# EDCPSU.net
KiCad netlist of a schematic drawn in EAGLE
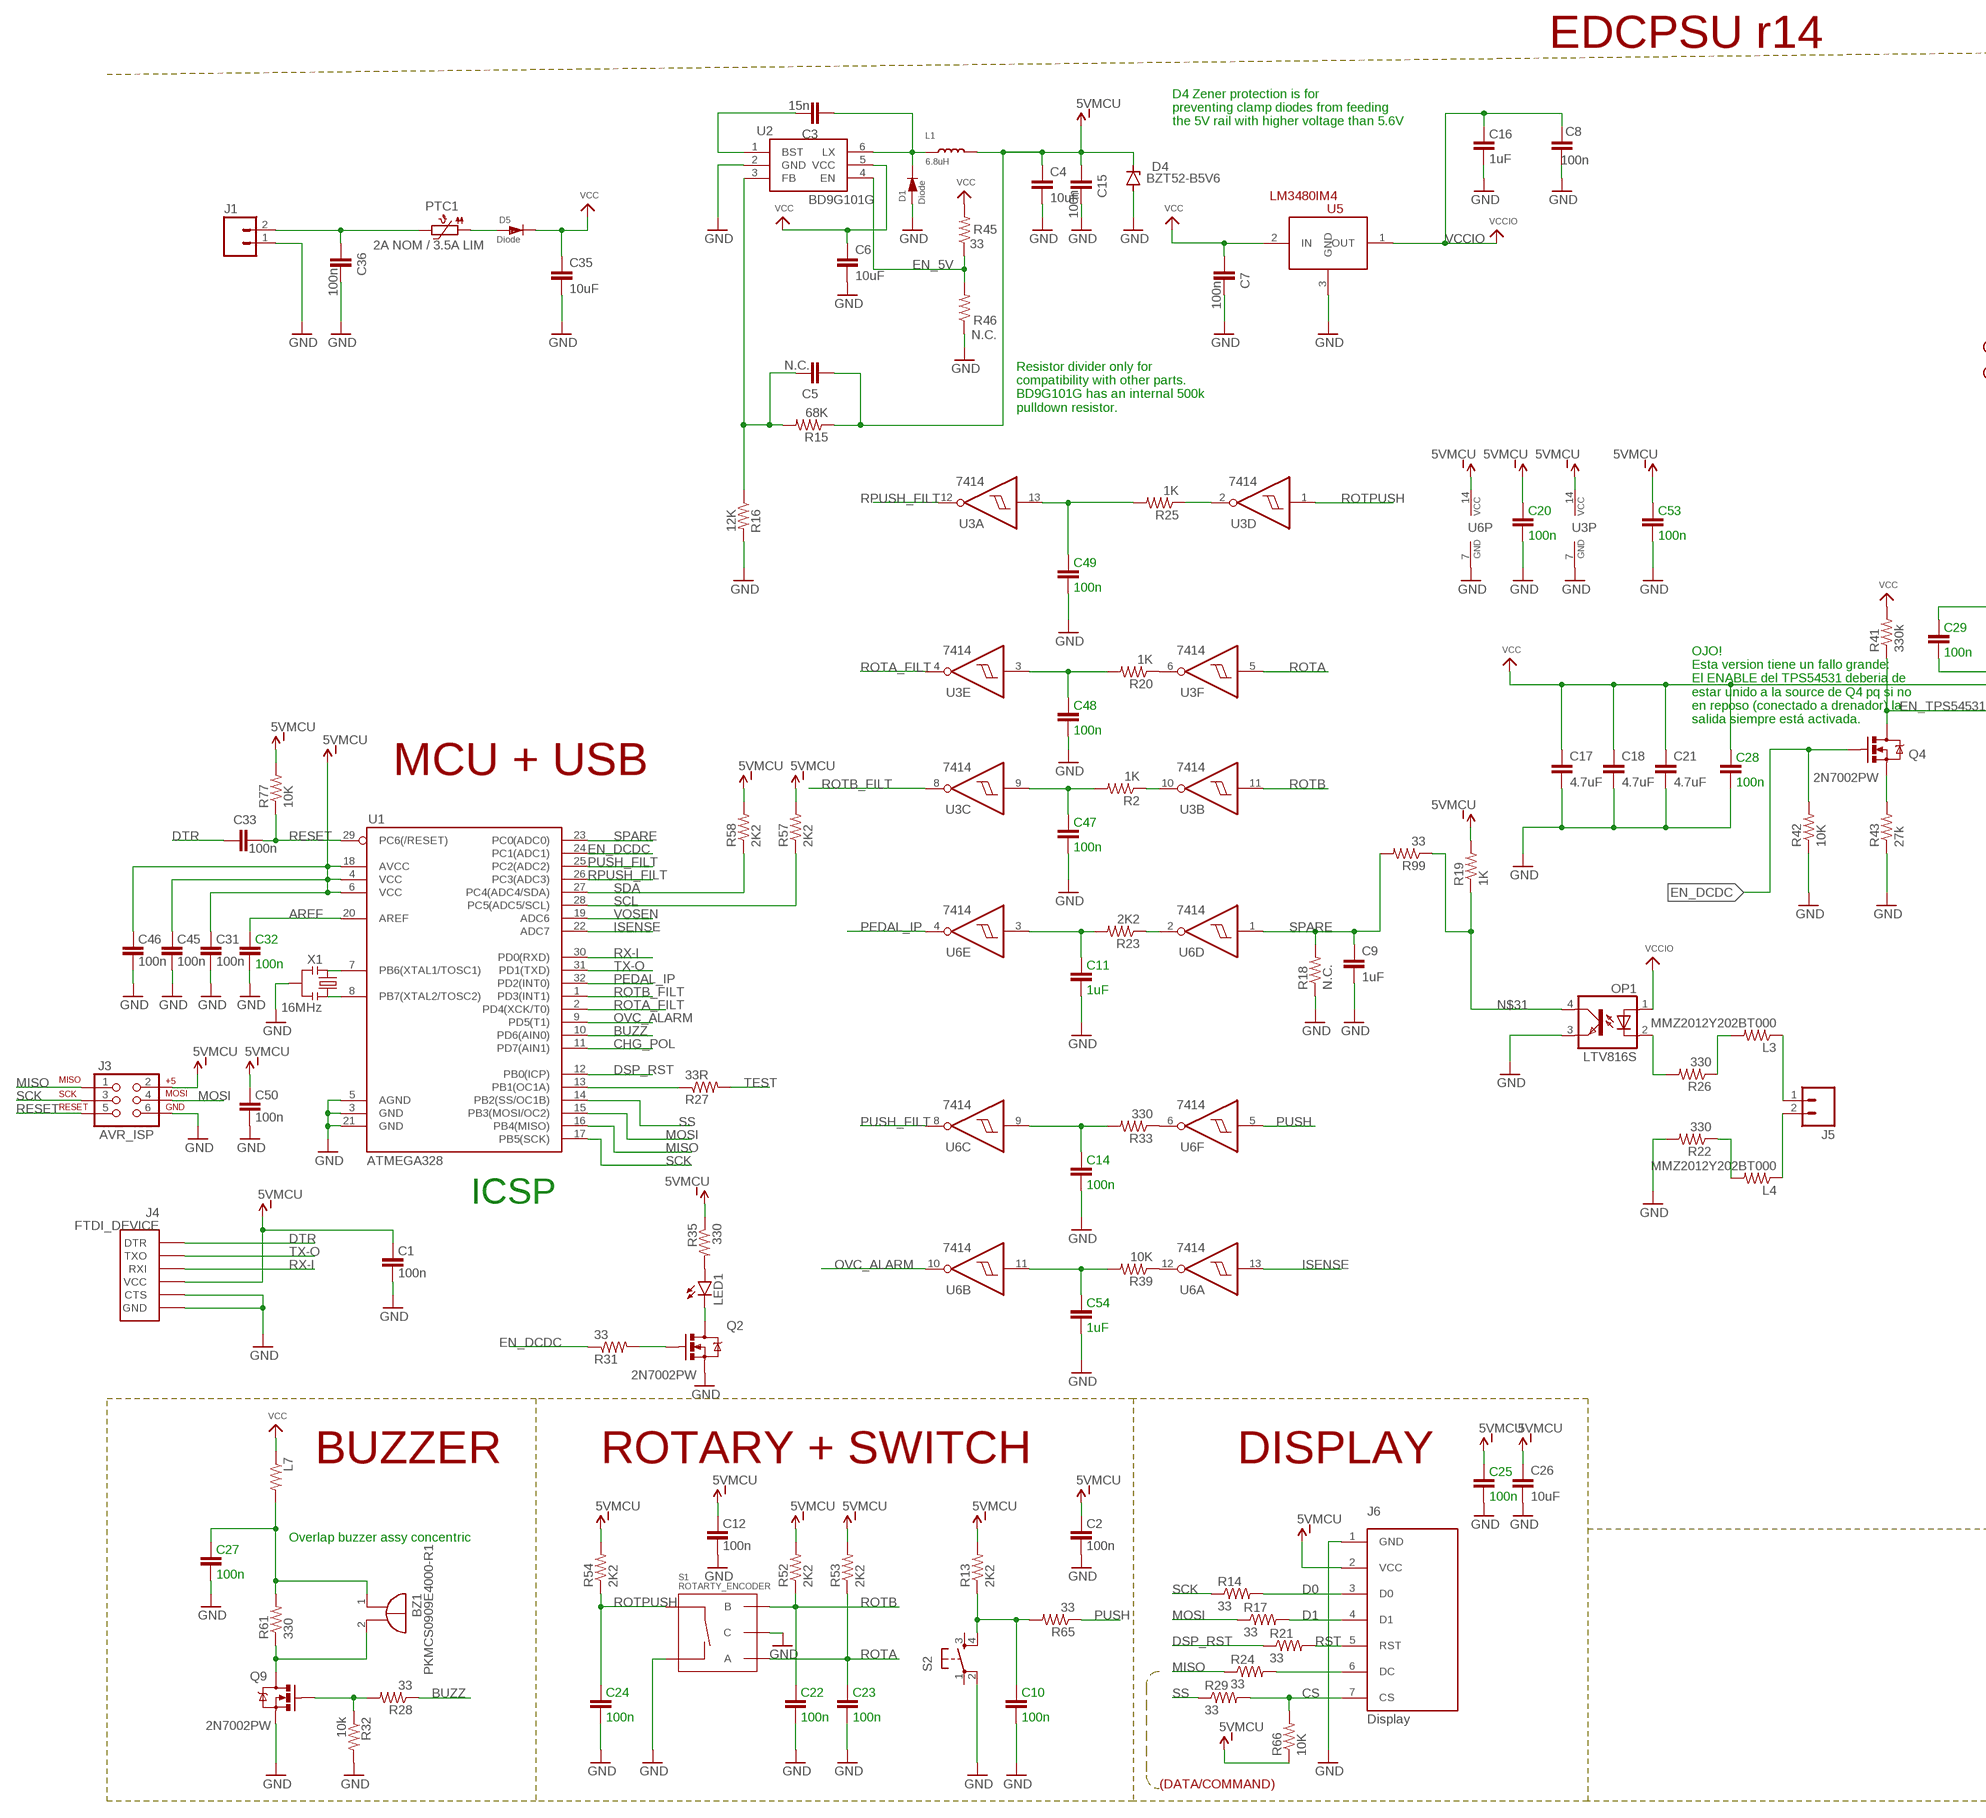
[diagram p0: schematic, sheet 1, part 1 of 2]
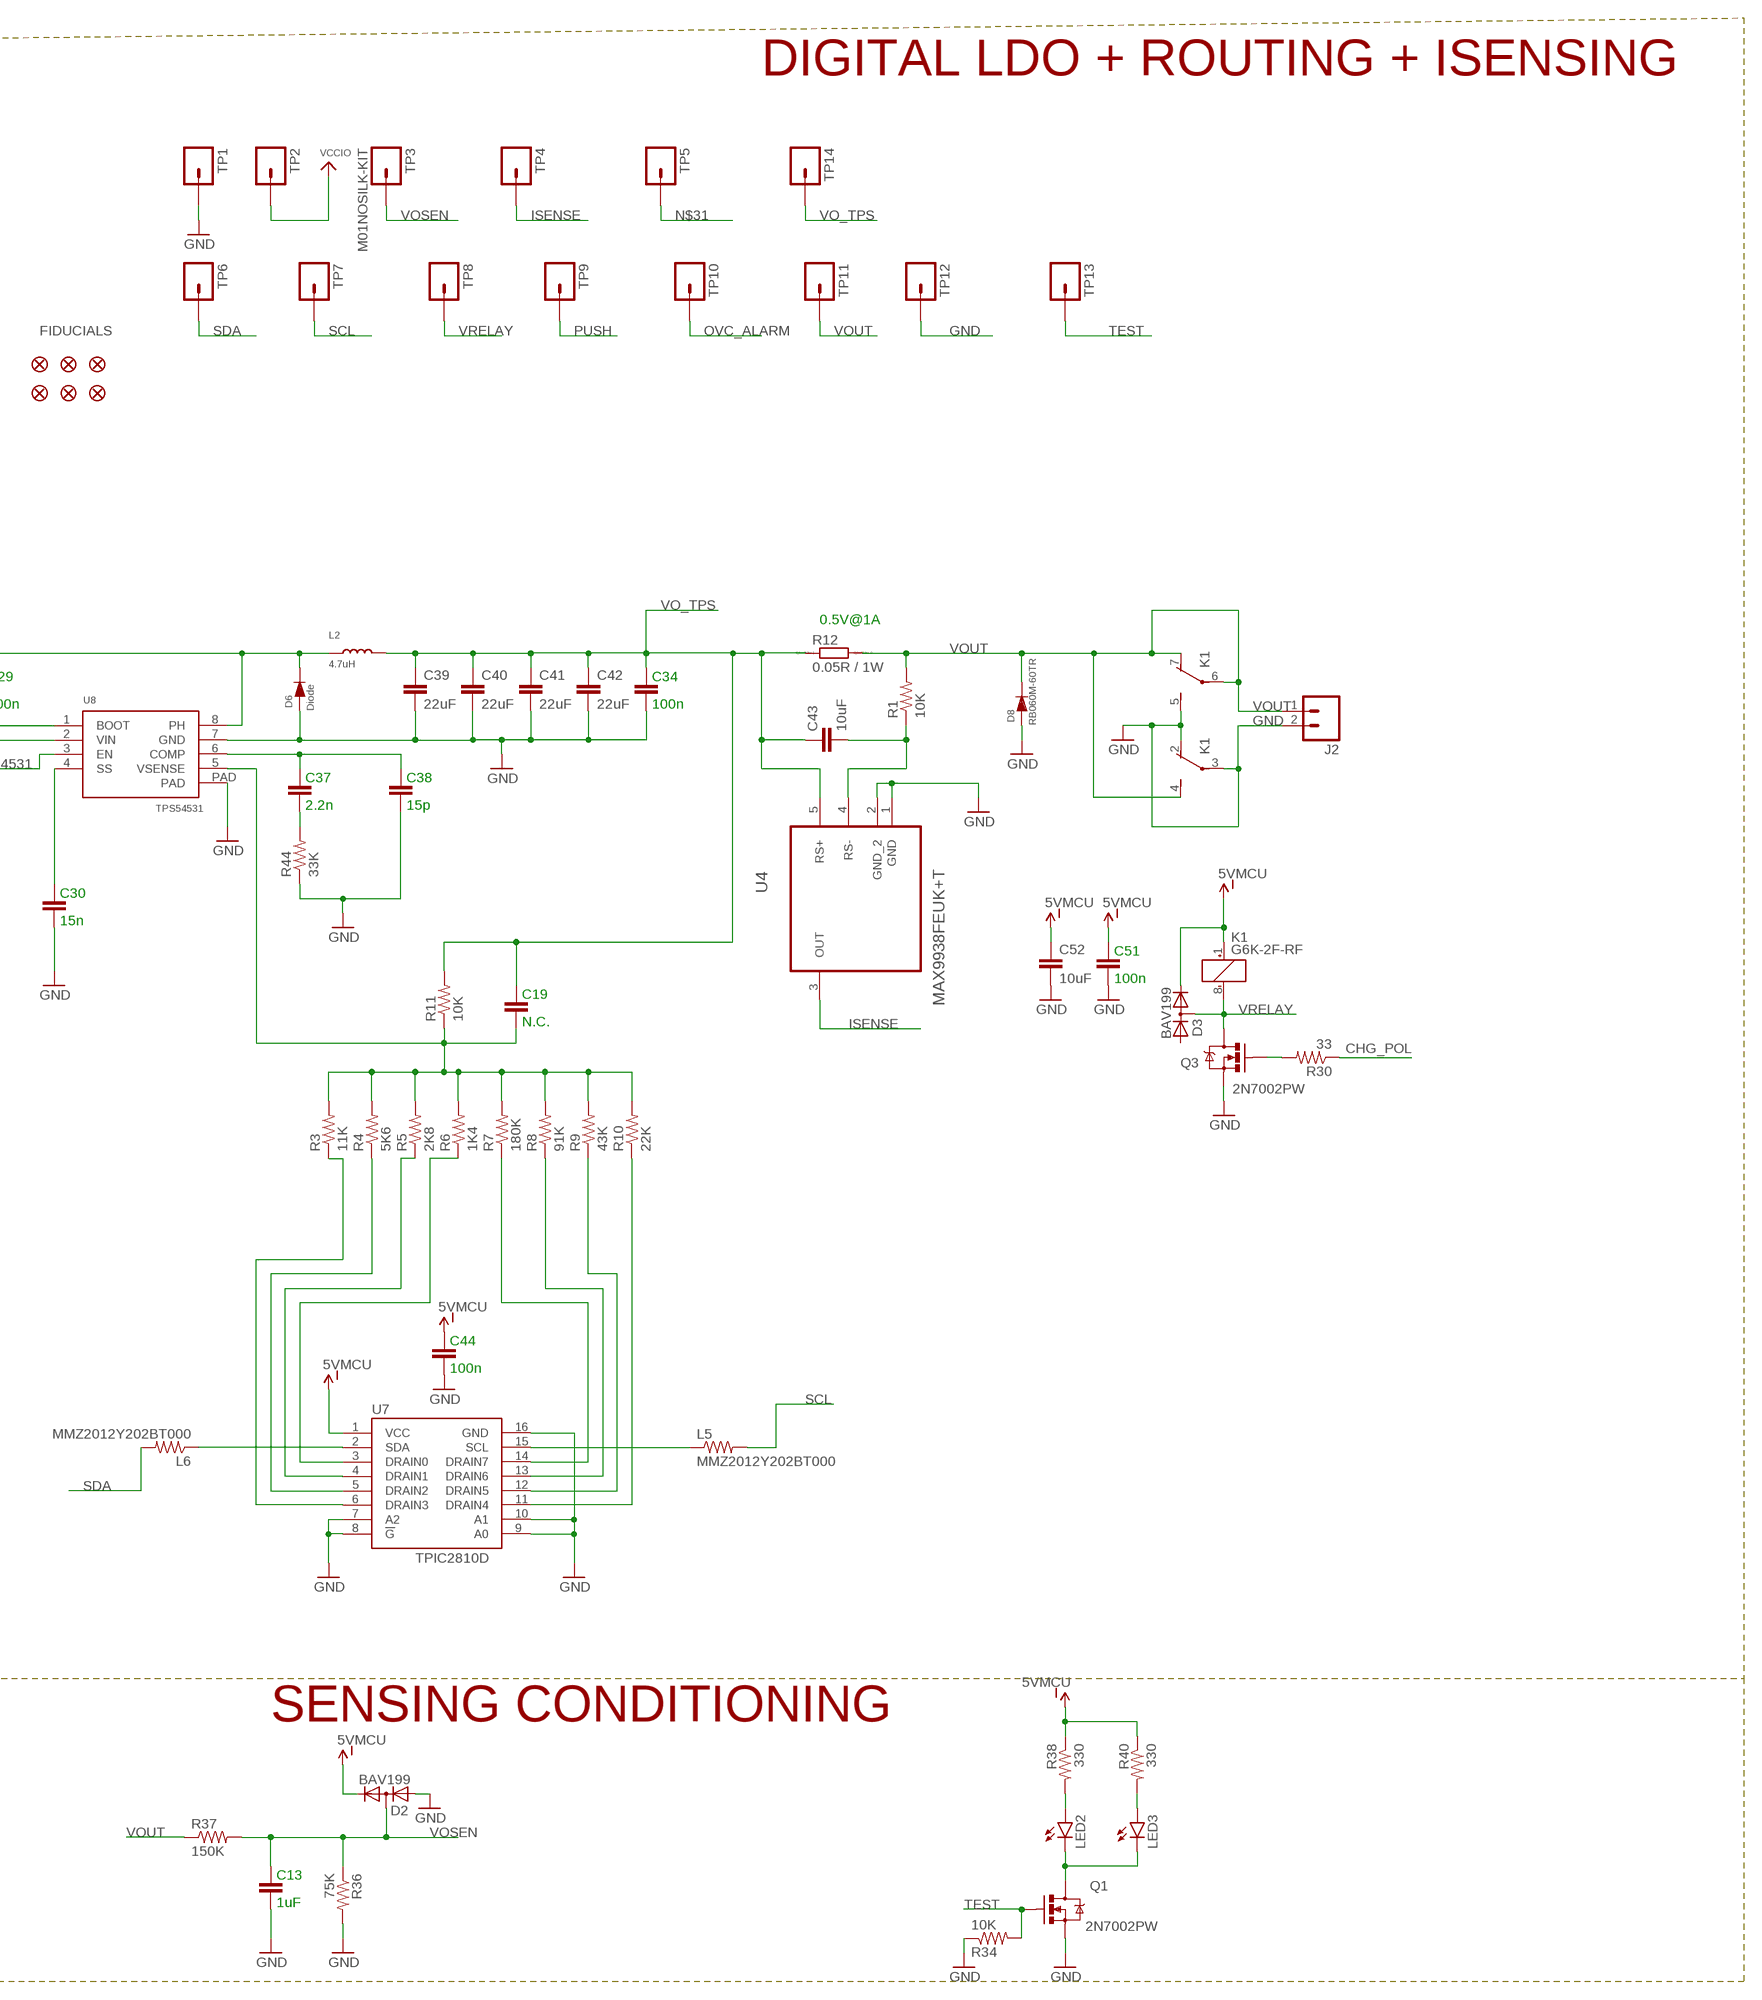
[diagram p1: schematic, sheet 1, part 2 of 2]

(export (version "E")
  (design (tool "Eeschema 10.0.6"))
  (components
    (comp (ref "BZ1")
      (value "PKMCS0909E4000-R1")
      (footprint "eagle-import:PKMCS0909")
      (libsource (lib "eagle-import") (part "PKMCS0909E4000-R1"))
    )
    (comp (ref "C1")
      (value "100n")
      (footprint "eagle-import:0805")
      (libsource (lib "eagle-import") (part "CAP0805"))
    )
    (comp (ref "C2")
      (value "100n")
      (footprint "eagle-import:0805")
      (libsource (lib "eagle-import") (part "CAP0805"))
    )
    (comp (ref "C3")
      (value "15n")
      (footprint "eagle-import:0805")
      (libsource (lib "eagle-import") (part "CAP0805"))
    )
    (comp (ref "C4")
      (value "10uF")
      (footprint "eagle-import:1206")
      (libsource (lib "eagle-import") (part "SparkFun-Passives_CAP1206"))
    )
    (comp (ref "C5")
      (value "N.C.")
      (footprint "eagle-import:0805")
      (libsource (lib "eagle-import") (part "CAP0805"))
    )
    (comp (ref "C6")
      (value "10uF")
      (footprint "eagle-import:1206")
      (libsource (lib "eagle-import") (part "SparkFun-Passives_CAP1206"))
    )
    (comp (ref "C7")
      (value "100n")
      (footprint "eagle-import:0805")
      (libsource (lib "eagle-import") (part "CAP0805"))
    )
    (comp (ref "C8")
      (value "100n")
      (footprint "eagle-import:0805")
      (libsource (lib "eagle-import") (part "CAP0805"))
    )
    (comp (ref "C9")
      (value "1uF")
      (footprint "eagle-import:1206")
      (libsource (lib "eagle-import") (part "SparkFun-Passives_CAP1206"))
    )
    (comp (ref "C10")
      (value "100n")
      (footprint "eagle-import:0805")
      (libsource (lib "eagle-import") (part "CAP0805"))
    )
    (comp (ref "C11")
      (value "1uF")
      (footprint "eagle-import:0805")
      (libsource (lib "eagle-import") (part "CAP0805"))
    )
    (comp (ref "C12")
      (value "100n")
      (footprint "eagle-import:0805")
      (libsource (lib "eagle-import") (part "CAP0805"))
    )
    (comp (ref "C13")
      (value "1uF")
      (footprint "eagle-import:0805")
      (libsource (lib "eagle-import") (part "CAP0805"))
    )
    (comp (ref "C14")
      (value "100n")
      (footprint "eagle-import:0805")
      (libsource (lib "eagle-import") (part "CAP0805"))
    )
    (comp (ref "C15")
      (value "100n")
      (footprint "eagle-import:0805")
      (libsource (lib "eagle-import") (part "CAP0805"))
    )
    (comp (ref "C16")
      (value "1uF")
      (footprint "eagle-import:0805")
      (libsource (lib "eagle-import") (part "CAP0805"))
    )
    (comp (ref "C17")
      (value "4.7uF")
      (footprint "eagle-import:1210")
      (libsource (lib "eagle-import") (part "SparkFun-Passives_CAP1210"))
    )
    (comp (ref "C18")
      (value "4.7uF")
      (footprint "eagle-import:1210")
      (libsource (lib "eagle-import") (part "SparkFun-Passives_CAP1210"))
    )
    (comp (ref "C19")
      (value "N.C.")
      (footprint "eagle-import:0805")
      (libsource (lib "eagle-import") (part "CAP0805"))
    )
    (comp (ref "C20")
      (value "100n")
      (footprint "eagle-import:0805")
      (libsource (lib "eagle-import") (part "CAP0805"))
    )
    (comp (ref "C21")
      (value "4.7uF")
      (footprint "eagle-import:1210")
      (libsource (lib "eagle-import") (part "SparkFun-Passives_CAP1210"))
    )
    (comp (ref "C22")
      (value "100n")
      (footprint "eagle-import:0805")
      (libsource (lib "eagle-import") (part "CAP0805"))
    )
    (comp (ref "C23")
      (value "100n")
      (footprint "eagle-import:0805")
      (libsource (lib "eagle-import") (part "CAP0805"))
    )
    (comp (ref "C24")
      (value "100n")
      (footprint "eagle-import:0805")
      (libsource (lib "eagle-import") (part "CAP0805"))
    )
    (comp (ref "C25")
      (value "100n")
      (footprint "eagle-import:0805")
      (libsource (lib "eagle-import") (part "CAP0805"))
    )
    (comp (ref "C26")
      (value "10uF")
      (footprint "eagle-import:1206")
      (libsource (lib "eagle-import") (part "SparkFun-Passives_CAP1206"))
    )
    (comp (ref "C27")
      (value "100n")
      (footprint "eagle-import:0805")
      (libsource (lib "eagle-import") (part "CAP0805"))
    )
    (comp (ref "C28")
      (value "100n")
      (footprint "eagle-import:0805")
      (libsource (lib "eagle-import") (part "CAP0805"))
    )
    (comp (ref "C29")
      (value "100n")
      (footprint "eagle-import:0805")
      (libsource (lib "eagle-import") (part "CAP0805"))
    )
    (comp (ref "C30")
      (value "15n")
      (footprint "eagle-import:0805")
      (libsource (lib "eagle-import") (part "CAP0805"))
    )
    (comp (ref "C31")
      (value "100n")
      (footprint "eagle-import:0805")
      (libsource (lib "eagle-import") (part "CAP0805"))
    )
    (comp (ref "C32")
      (value "100n")
      (footprint "eagle-import:0805")
      (libsource (lib "eagle-import") (part "CAP0805"))
    )
    (comp (ref "C33")
      (value "100n")
      (footprint "eagle-import:0805")
      (libsource (lib "eagle-import") (part "CAP0805"))
    )
    (comp (ref "C34")
      (value "100n")
      (footprint "eagle-import:0805")
      (libsource (lib "eagle-import") (part "CAP0805"))
    )
    (comp (ref "C35")
      (value "10uF")
      (footprint "eagle-import:1206")
      (libsource (lib "eagle-import") (part "SparkFun-Passives_CAP1206"))
    )
    (comp (ref "C36")
      (value "100n")
      (footprint "eagle-import:0805")
      (libsource (lib "eagle-import") (part "CAP0805"))
    )
    (comp (ref "C37")
      (value "2.2n")
      (footprint "eagle-import:0805")
      (libsource (lib "eagle-import") (part "CAP0805"))
    )
    (comp (ref "C38")
      (value "15p")
      (footprint "eagle-import:0805")
      (libsource (lib "eagle-import") (part "CAP0805"))
    )
    (comp (ref "C39")
      (value "22uF")
      (footprint "eagle-import:1210")
      (libsource (lib "eagle-import") (part "SparkFun-Passives_CAP1210"))
    )
    (comp (ref "C40")
      (value "22uF")
      (footprint "eagle-import:1210")
      (libsource (lib "eagle-import") (part "SparkFun-Passives_CAP1210"))
    )
    (comp (ref "C41")
      (value "22uF")
      (footprint "eagle-import:1210")
      (libsource (lib "eagle-import") (part "SparkFun-Passives_CAP1210"))
    )
    (comp (ref "C42")
      (value "22uF")
      (footprint "eagle-import:1210")
      (libsource (lib "eagle-import") (part "SparkFun-Passives_CAP1210"))
    )
    (comp (ref "C43")
      (value "10uF")
      (footprint "eagle-import:1206")
      (libsource (lib "eagle-import") (part "SparkFun-Passives_CAP1206"))
    )
    (comp (ref "C44")
      (value "100n")
      (footprint "eagle-import:0805")
      (libsource (lib "eagle-import") (part "CAP0805"))
    )
    (comp (ref "C45")
      (value "100n")
      (footprint "eagle-import:0805")
      (libsource (lib "eagle-import") (part "CAP0805"))
    )
    (comp (ref "C46")
      (value "100n")
      (footprint "eagle-import:0805")
      (libsource (lib "eagle-import") (part "CAP0805"))
    )
    (comp (ref "C47")
      (value "100n")
      (footprint "eagle-import:0805")
      (libsource (lib "eagle-import") (part "CAP0805"))
    )
    (comp (ref "C48")
      (value "100n")
      (footprint "eagle-import:0805")
      (libsource (lib "eagle-import") (part "CAP0805"))
    )
    (comp (ref "C49")
      (value "100n")
      (footprint "eagle-import:0805")
      (libsource (lib "eagle-import") (part "CAP0805"))
    )
    (comp (ref "C50")
      (value "100n")
      (footprint "eagle-import:0805")
      (libsource (lib "eagle-import") (part "CAP0805"))
    )
    (comp (ref "C51")
      (value "100n")
      (footprint "eagle-import:0805")
      (libsource (lib "eagle-import") (part "CAP0805"))
    )
    (comp (ref "C52")
      (value "10uF")
      (footprint "eagle-import:1206")
      (libsource (lib "eagle-import") (part "SparkFun-Passives_CAP1206"))
    )
    (comp (ref "C53")
      (value "100n")
      (footprint "eagle-import:0805")
      (libsource (lib "eagle-import") (part "CAP0805"))
    )
    (comp (ref "C54")
      (value "1uF")
      (footprint "eagle-import:0805")
      (libsource (lib "eagle-import") (part "CAP0805"))
    )
    (comp (ref "D1")
      (value "Diode")
      (footprint "eagle-import:SOD123")
      (libsource (lib "eagle-import") (part "DSOD123"))
    )
    (comp (ref "D2")
      (value "BAV199")
      (footprint "eagle-import:SOT23")
      (libsource (lib "eagle-import") (part "BAV199"))
    )
    (comp (ref "D3")
      (value "BAV199")
      (footprint "eagle-import:SOT23")
      (libsource (lib "eagle-import") (part "BAV199"))
    )
    (comp (ref "D4")
      (value "BZT52-B5V6")
      (footprint "eagle-import:SODFL3718X115")
      (libsource (lib "eagle-import") (part "ZENERDO-219-AB(SOD123F)_"))
    )
    (comp (ref "D5")
      (value "Diode")
      (footprint "eagle-import:DO-214AB")
      (libsource (lib "eagle-import") (part "DSMC"))
    )
    (comp (ref "D6")
      (value "Diode")
      (footprint "eagle-import:DO-214AB")
      (libsource (lib "eagle-import") (part "DSMC"))
    )
    (comp (ref "D8")
      (value "RB060M-60TR")
      (footprint "eagle-import:SMADIODE")
      (libsource (lib "eagle-import") (part "DSMA"))
    )
    (comp (ref "FID1")
      (value "FIDUCIAL1X2")
      (footprint "eagle-import:FIDUCIAL-1X2")
      (libsource (lib "eagle-import") (part "FIDUCIAL1X2"))
    )
    (comp (ref "FID2")
      (value "FIDUCIAL1X2")
      (footprint "eagle-import:FIDUCIAL-1X2")
      (libsource (lib "eagle-import") (part "FIDUCIAL1X2"))
    )
    (comp (ref "FID3")
      (value "FIDUCIAL1X2")
      (footprint "eagle-import:FIDUCIAL-1X2")
      (libsource (lib "eagle-import") (part "FIDUCIAL1X2"))
    )
    (comp (ref "FID4")
      (value "FIDUCIAL1X2")
      (footprint "eagle-import:FIDUCIAL-1X2")
      (libsource (lib "eagle-import") (part "FIDUCIAL1X2"))
    )
    (comp (ref "FID5")
      (value "FIDUCIAL1X2")
      (footprint "eagle-import:FIDUCIAL-1X2")
      (libsource (lib "eagle-import") (part "FIDUCIAL1X2"))
    )
    (comp (ref "FID6")
      (value "FIDUCIAL1X2")
      (footprint "eagle-import:FIDUCIAL-1X2")
      (libsource (lib "eagle-import") (part "FIDUCIAL1X2"))
    )
    (comp (ref "J1")
      (value "M02LOCK_LONGPADS")
      (footprint "eagle-import:1X02_LOCK_LONGPADS")
      (libsource (lib "eagle-import") (part "M02LOCK_LONGPADS"))
    )
    (comp (ref "J2")
      (value "M02LOCK_LONGPADS")
      (footprint "eagle-import:1X02_LOCK_LONGPADS")
      (libsource (lib "eagle-import") (part "M02LOCK_LONGPADS"))
    )
    (comp (ref "J3")
      (value "AVR_ISP")
      (footprint "eagle-import:2X3")
      (libsource (lib "eagle-import") (part "AVR_SPI_PRG_6PTH"))
    )
    (comp (ref "J4")
      (value "FTDI_DEVICE")
      (footprint "eagle-import:FTDI_DEVICE_SIDE")
      (libsource (lib "eagle-import") (part "FTDI_DEVICE"))
    )
    (comp (ref "J5")
      (value "M02LOCK_LONGPADS")
      (footprint "eagle-import:1X02_LOCK_LONGPADS")
      (libsource (lib "eagle-import") (part "M02LOCK_LONGPADS"))
    )
    (comp (ref "J6")
      (value "Display")
      (footprint "eagle-import:OLED_LCD")
      (libsource (lib "eagle-import") (part "OLED_LCD"))
    )
    (comp (ref "K1")
      (value "G6K-2F-RF")
      (footprint "eagle-import:G6K-RF")
      (fields (field (name "MF") "OMRON COMPONENTS USA") (field (name "MPN") "G6K-2F-RF-DC12"))
      (libsource (lib "eagle-import") (part "G6K-2F-RF"))
    )
    (comp (ref "L1")
      (value "6.8uH")
      (footprint "eagle-import:NR4018T100M")
      (libsource (lib "eagle-import") (part "L4018"))
    )
    (comp (ref "L2")
      (value "4.7uH")
      (footprint "eagle-import:WE-LHMI")
      (libsource (lib "eagle-import") (part "L74437368047"))
    )
    (comp (ref "L3")
      (value "MMZ2012Y202BT000")
      (footprint "eagle-import:0805")
      (libsource (lib "eagle-import") (part "RESISTOR0805-RES"))
    )
    (comp (ref "L4")
      (value "MMZ2012Y202BT000")
      (footprint "eagle-import:0805")
      (libsource (lib "eagle-import") (part "RESISTOR0805-RES"))
    )
    (comp (ref "L5")
      (value "MMZ2012Y202BT000")
      (footprint "eagle-import:0805")
      (libsource (lib "eagle-import") (part "RESISTOR0805-RES"))
    )
    (comp (ref "L6")
      (value "MMZ2012Y202BT000")
      (footprint "eagle-import:0805")
      (libsource (lib "eagle-import") (part "RESISTOR0805-RES"))
    )
    (comp (ref "L7")
      (value "MMZ2012Y202BT000")
      (footprint "eagle-import:0805")
      (libsource (lib "eagle-import") (part "RESISTOR0805-RES"))
    )
    (comp (ref "LED1")
      (value "LED3MM")
      (footprint "eagle-import:LED3MM")
      (libsource (lib "eagle-import") (part "LED3MM"))
    )
    (comp (ref "LED2")
      (value "LED5MM")
      (footprint "eagle-import:LED5MM")
      (libsource (lib "eagle-import") (part "LED5MM"))
    )
    (comp (ref "LED3")
      (value "LED5MM")
      (footprint "eagle-import:LED5MM")
      (libsource (lib "eagle-import") (part "LED5MM"))
    )
    (comp (ref "OP1")
      (value "LTV816S")
      (footprint "eagle-import:SMD4")
      (libsource (lib "eagle-import") (part "LTV816S"))
    )
    (comp (ref "PTC1")
      (value "2A NOM / 3.5A LIM")
      (footprint "eagle-import:1812L")
      (libsource (lib "eagle-import") (part "PTC-"))
    )
    (comp (ref "Q1")
      (value "2N7002PW")
      (footprint "eagle-import:SOT323")
      (libsource (lib "eagle-import") (part "MOSFET-NCHANNEL2N7002PW"))
    )
    (comp (ref "Q2")
      (value "2N7002PW")
      (footprint "eagle-import:SOT323")
      (libsource (lib "eagle-import") (part "MOSFET-NCHANNEL2N7002PW"))
    )
    (comp (ref "Q3")
      (value "2N7002PW")
      (footprint "eagle-import:SOT323")
      (libsource (lib "eagle-import") (part "MOSFET-NCHANNEL2N7002PW"))
    )
    (comp (ref "Q4")
      (value "2N7002PW")
      (footprint "eagle-import:SOT323")
      (libsource (lib "eagle-import") (part "MOSFET-NCHANNEL2N7002PW"))
    )
    (comp (ref "Q9")
      (value "2N7002PW")
      (footprint "eagle-import:SOT323")
      (libsource (lib "eagle-import") (part "MOSFET-NCHANNEL2N7002PW"))
    )
    (comp (ref "R1")
      (value "10K")
      (footprint "eagle-import:0805")
      (libsource (lib "eagle-import") (part "RESISTOR0805-RES"))
    )
    (comp (ref "R2")
      (value "1K")
      (footprint "eagle-import:0805")
      (libsource (lib "eagle-import") (part "RESISTOR0805-RES"))
    )
    (comp (ref "R3")
      (value "11K")
      (footprint "eagle-import:0805")
      (libsource (lib "eagle-import") (part "RESISTOR0805-RES"))
    )
    (comp (ref "R4")
      (value "5K6")
      (footprint "eagle-import:0805")
      (libsource (lib "eagle-import") (part "RESISTOR0805-RES"))
    )
    (comp (ref "R5")
      (value "2K8")
      (footprint "eagle-import:0805")
      (libsource (lib "eagle-import") (part "RESISTOR0805-RES"))
    )
    (comp (ref "R6")
      (value "1K4")
      (footprint "eagle-import:0805")
      (libsource (lib "eagle-import") (part "RESISTOR0805-RES"))
    )
    (comp (ref "R7")
      (value "180K")
      (footprint "eagle-import:0805")
      (libsource (lib "eagle-import") (part "RESISTOR0805-RES"))
    )
    (comp (ref "R8")
      (value "91K")
      (footprint "eagle-import:0805")
      (libsource (lib "eagle-import") (part "RESISTOR0805-RES"))
    )
    (comp (ref "R9")
      (value "43K")
      (footprint "eagle-import:0805")
      (libsource (lib "eagle-import") (part "RESISTOR0805-RES"))
    )
    (comp (ref "R10")
      (value "22K")
      (footprint "eagle-import:0805")
      (libsource (lib "eagle-import") (part "RESISTOR0805-RES"))
    )
    (comp (ref "R11")
      (value "10K")
      (footprint "eagle-import:0805")
      (libsource (lib "eagle-import") (part "RESISTOR0805-RES"))
    )
    (comp (ref "R12")
      (value "0.05R / 1W")
      (footprint "eagle-import:R2512")
      (libsource (lib "eagle-import") (part "RR2512"))
    )
    (comp (ref "R13")
      (value "2K2")
      (footprint "eagle-import:0805")
      (libsource (lib "eagle-import") (part "RESISTOR0805-RES"))
    )
    (comp (ref "R14")
      (value "33")
      (footprint "eagle-import:0805")
      (libsource (lib "eagle-import") (part "RESISTOR0805-RES"))
    )
    (comp (ref "R15")
      (value "68K")
      (footprint "eagle-import:0805")
      (libsource (lib "eagle-import") (part "RESISTOR0805-RES"))
    )
    (comp (ref "R16")
      (value "12K")
      (footprint "eagle-import:0805")
      (libsource (lib "eagle-import") (part "RESISTOR0805-RES"))
    )
    (comp (ref "R17")
      (value "33")
      (footprint "eagle-import:0805")
      (libsource (lib "eagle-import") (part "RESISTOR0805-RES"))
    )
    (comp (ref "R18")
      (value "N.C.")
      (footprint "eagle-import:0805")
      (libsource (lib "eagle-import") (part "RESISTOR0805-RES"))
    )
    (comp (ref "R19")
      (value "1K")
      (footprint "eagle-import:0805")
      (libsource (lib "eagle-import") (part "RESISTOR0805-RES"))
    )
    (comp (ref "R20")
      (value "1K")
      (footprint "eagle-import:0805")
      (libsource (lib "eagle-import") (part "RESISTOR0805-RES"))
    )
    (comp (ref "R21")
      (value "33")
      (footprint "eagle-import:0805")
      (libsource (lib "eagle-import") (part "RESISTOR0805-RES"))
    )
    (comp (ref "R22")
      (value "330")
      (footprint "eagle-import:1206")
      (libsource (lib "eagle-import") (part "SparkFun-Passives_RESISTOR1206"))
    )
    (comp (ref "R23")
      (value "2K2")
      (footprint "eagle-import:0805")
      (libsource (lib "eagle-import") (part "RESISTOR0805-RES"))
    )
    (comp (ref "R24")
      (value "33")
      (footprint "eagle-import:0805")
      (libsource (lib "eagle-import") (part "RESISTOR0805-RES"))
    )
    (comp (ref "R25")
      (value "1K")
      (footprint "eagle-import:0805")
      (libsource (lib "eagle-import") (part "RESISTOR0805-RES"))
    )
    (comp (ref "R26")
      (value "330")
      (footprint "eagle-import:1206")
      (libsource (lib "eagle-import") (part "SparkFun-Passives_RESISTOR1206"))
    )
    (comp (ref "R27")
      (value "33R")
      (footprint "eagle-import:0805")
      (libsource (lib "eagle-import") (part "RESISTOR0805-RES"))
    )
    (comp (ref "R28")
      (value "33")
      (footprint "eagle-import:0805")
      (libsource (lib "eagle-import") (part "RESISTOR0805-RES"))
    )
    (comp (ref "R29")
      (value "33")
      (footprint "eagle-import:0805")
      (libsource (lib "eagle-import") (part "RESISTOR0805-RES"))
    )
    (comp (ref "R30")
      (value "33")
      (footprint "eagle-import:0805")
      (libsource (lib "eagle-import") (part "RESISTOR0805-RES"))
    )
    (comp (ref "R31")
      (value "33")
      (footprint "eagle-import:0805")
      (libsource (lib "eagle-import") (part "RESISTOR0805-RES"))
    )
    (comp (ref "R32")
      (value "10k")
      (footprint "eagle-import:0805")
      (libsource (lib "eagle-import") (part "RESISTOR0805-RES"))
    )
    (comp (ref "R33")
      (value "330")
      (footprint "eagle-import:0805")
      (libsource (lib "eagle-import") (part "RESISTOR0805-RES"))
    )
    (comp (ref "R34")
      (value "10K")
      (footprint "eagle-import:0805")
      (libsource (lib "eagle-import") (part "RESISTOR0805-RES"))
    )
    (comp (ref "R35")
      (value "330")
      (footprint "eagle-import:0805")
      (libsource (lib "eagle-import") (part "RESISTOR0805-RES"))
    )
    (comp (ref "R36")
      (value "75K")
      (footprint "eagle-import:0805")
      (libsource (lib "eagle-import") (part "RESISTOR0805-RES"))
    )
    (comp (ref "R37")
      (value "150K")
      (footprint "eagle-import:0805")
      (libsource (lib "eagle-import") (part "RESISTOR0805-RES"))
    )
    (comp (ref "R38")
      (value "330")
      (footprint "eagle-import:0805")
      (libsource (lib "eagle-import") (part "RESISTOR0805-RES"))
    )
    (comp (ref "R39")
      (value "10K")
      (footprint "eagle-import:0805")
      (libsource (lib "eagle-import") (part "RESISTOR0805-RES"))
    )
    (comp (ref "R40")
      (value "330")
      (footprint "eagle-import:0805")
      (libsource (lib "eagle-import") (part "RESISTOR0805-RES"))
    )
    (comp (ref "R41")
      (value "330k")
      (footprint "eagle-import:0805")
      (libsource (lib "eagle-import") (part "RESISTOR0805-RES"))
    )
    (comp (ref "R42")
      (value "10K")
      (footprint "eagle-import:0805")
      (libsource (lib "eagle-import") (part "RESISTOR0805-RES"))
    )
    (comp (ref "R43")
      (value "27k")
      (footprint "eagle-import:0805")
      (libsource (lib "eagle-import") (part "RESISTOR0805-RES"))
    )
    (comp (ref "R44")
      (value "33K")
      (footprint "eagle-import:0805")
      (libsource (lib "eagle-import") (part "RESISTOR0805-RES"))
    )
    (comp (ref "R45")
      (value "33")
      (footprint "eagle-import:0805")
      (libsource (lib "eagle-import") (part "RESISTOR0805-RES"))
    )
    (comp (ref "R46")
      (value "N.C.")
      (footprint "eagle-import:0805")
      (libsource (lib "eagle-import") (part "RESISTOR0805-RES"))
    )
    (comp (ref "R52")
      (value "2K2")
      (footprint "eagle-import:0805")
      (libsource (lib "eagle-import") (part "RESISTOR0805-RES"))
    )
    (comp (ref "R53")
      (value "2K2")
      (footprint "eagle-import:0805")
      (libsource (lib "eagle-import") (part "RESISTOR0805-RES"))
    )
    (comp (ref "R54")
      (value "2K2")
      (footprint "eagle-import:0805")
      (libsource (lib "eagle-import") (part "RESISTOR0805-RES"))
    )
    (comp (ref "R57")
      (value "2K2")
      (footprint "eagle-import:0805")
      (libsource (lib "eagle-import") (part "RESISTOR0805-RES"))
    )
    (comp (ref "R58")
      (value "2K2")
      (footprint "eagle-import:0805")
      (libsource (lib "eagle-import") (part "RESISTOR0805-RES"))
    )
    (comp (ref "R61")
      (value "330")
      (footprint "eagle-import:0805")
      (libsource (lib "eagle-import") (part "RESISTOR0805-RES"))
    )
    (comp (ref "R65")
      (value "33")
      (footprint "eagle-import:0805")
      (libsource (lib "eagle-import") (part "RESISTOR0805-RES"))
    )
    (comp (ref "R66")
      (value "10K")
      (footprint "eagle-import:0805")
      (libsource (lib "eagle-import") (part "RESISTOR0805-RES"))
    )
    (comp (ref "R77")
      (value "10K")
      (footprint "eagle-import:0805")
      (libsource (lib "eagle-import") (part "RESISTOR0805-RES"))
    )
    (comp (ref "R99")
      (value "33")
      (footprint "eagle-import:0805")
      (libsource (lib "eagle-import") (part "RESISTOR0805-RES"))
    )
    (comp (ref "S1")
      (value "ROTARTY_ENCODER")
      (footprint "eagle-import:ROTARY_ENC_PLAIN")
      (libsource (lib "eagle-import") (part "ROTARTY_ENCODER"))
    )
    (comp (ref "S2")
      (value "TAC_SWITCH_KSC931G-SMD")
      (footprint "eagle-import:TAC_SW_SMD_KSC931G")
      (libsource (lib "eagle-import") (part "TAC_SWITCH_KSC931G-SMD"))
    )
    (comp (ref "TP1")
      (value "M01POGOPIN_HOLE_LARGE")
      (footprint "eagle-import:1X01_POGOPIN_HOLE_LARGE")
      (libsource (lib "eagle-import") (part "M01POGOPIN_HOLE_LARGE"))
    )
    (comp (ref "TP2")
      (value "M01POGOPIN_HOLE_LARGE")
      (footprint "eagle-import:1X01_POGOPIN_HOLE_LARGE")
      (libsource (lib "eagle-import") (part "M01POGOPIN_HOLE_LARGE"))
    )
    (comp (ref "TP3")
      (value "M01NOSILK-KIT")
      (footprint "eagle-import:1X01NS-KIT")
      (libsource (lib "eagle-import") (part "M01NOSILK-KIT"))
    )
    (comp (ref "TP4")
      (value "M01POGOPIN_HOLE_LARGE")
      (footprint "eagle-import:1X01_POGOPIN_HOLE_LARGE")
      (libsource (lib "eagle-import") (part "M01POGOPIN_HOLE_LARGE"))
    )
    (comp (ref "TP5")
      (value "M01POGOPIN_HOLE_LARGE")
      (footprint "eagle-import:1X01_POGOPIN_HOLE_LARGE")
      (libsource (lib "eagle-import") (part "M01POGOPIN_HOLE_LARGE"))
    )
    (comp (ref "TP6")
      (value "M01POGOPIN_HOLE_LARGE")
      (footprint "eagle-import:1X01_POGOPIN_HOLE_LARGE")
      (libsource (lib "eagle-import") (part "M01POGOPIN_HOLE_LARGE"))
    )
    (comp (ref "TP7")
      (value "M01POGOPIN_HOLE_LARGE")
      (footprint "eagle-import:1X01_POGOPIN_HOLE_LARGE")
      (libsource (lib "eagle-import") (part "M01POGOPIN_HOLE_LARGE"))
    )
    (comp (ref "TP8")
      (value "M01POGOPIN_HOLE_LARGE")
      (footprint "eagle-import:1X01_POGOPIN_HOLE_LARGE")
      (libsource (lib "eagle-import") (part "M01POGOPIN_HOLE_LARGE"))
    )
    (comp (ref "TP9")
      (value "M01POGOPIN_HOLE_LARGE")
      (footprint "eagle-import:1X01_POGOPIN_HOLE_LARGE")
      (libsource (lib "eagle-import") (part "M01POGOPIN_HOLE_LARGE"))
    )
    (comp (ref "TP10")
      (value "M01POGOPIN_HOLE_LARGE")
      (footprint "eagle-import:1X01_POGOPIN_HOLE_LARGE")
      (libsource (lib "eagle-import") (part "M01POGOPIN_HOLE_LARGE"))
    )
    (comp (ref "TP11")
      (value "M01POGOPIN_HOLE_LARGE")
      (footprint "eagle-import:1X01_POGOPIN_HOLE_LARGE")
      (libsource (lib "eagle-import") (part "M01POGOPIN_HOLE_LARGE"))
    )
    (comp (ref "TP12")
      (value "M01POGOPIN_HOLE_LARGE")
      (footprint "eagle-import:1X01_POGOPIN_HOLE_LARGE")
      (libsource (lib "eagle-import") (part "M01POGOPIN_HOLE_LARGE"))
    )
    (comp (ref "TP13")
      (value "M01POGOPIN_HOLE_LARGE")
      (footprint "eagle-import:1X01_POGOPIN_HOLE_LARGE")
      (libsource (lib "eagle-import") (part "M01POGOPIN_HOLE_LARGE"))
    )
    (comp (ref "TP14")
      (value "M01POGOPIN_HOLE_LARGE")
      (footprint "eagle-import:1X01_POGOPIN_HOLE_LARGE")
      (libsource (lib "eagle-import") (part "M01POGOPIN_HOLE_LARGE"))
    )
    (comp (ref "U1")
      (value "ATMEGA328")
      (footprint "eagle-import:TQFP32-08")
      (libsource (lib "eagle-import") (part "ATMEGA168"))
    )
    (comp (ref "U2")
      (value "BD9G101G")
      (footprint "eagle-import:SSOP6")
      (libsource (lib "eagle-import") (part "BD9G101G"))
    )
    (comp (ref "U3")
      (value "7414")
      (footprint "eagle-import:TSSOP14")
      (libsource (lib "eagle-import") (part "7414"))
    )
    (comp (ref "U4")
      (value "MAX9938FEUK+T")
      (footprint "eagle-import:SOT95P280X145-5N")
      (libsource (lib "eagle-import") (part "MAX9938FEUK+T"))
    )
    (comp (ref "U5")
      (value "LM3480IM4")
      (footprint "eagle-import:SOT23-3")
      (libsource (lib "eagle-import") (part "LM3480IM4"))
    )
    (comp (ref "U6")
      (value "7414")
      (footprint "eagle-import:TSSOP14")
      (libsource (lib "eagle-import") (part "7414"))
    )
    (comp (ref "U7")
      (value "TPIC2810D")
      (footprint "eagle-import:SO16")
      (libsource (lib "eagle-import") (part "TPIC2810D"))
    )
    (comp (ref "U8")
      (value "TPS54531")
      (footprint "eagle-import:SOIC8")
      (libsource (lib "eagle-import") (part "TPS5431DDAR"))
    )
    (comp (ref "X1")
      (value "16MHz")
      (footprint "eagle-import:RESONATOR-SMD")
      (libsource (lib "eagle-import") (part "RESONATORSMD"))
    )
  )
  (nets
    (net (code "1") (name "/AREF") (class "Default")
      (node (ref "C32") (pin "2") (pinfunction "2_2") (pintype "passive"))
      (node (ref "U1") (pin "20") (pinfunction "AREF_20") (pintype "bidirectional"))
    )
    (net (code "2") (name "/BUZZ") (class "Default")
      (node (ref "R28") (pin "1") (pinfunction "1_1") (pintype "passive"))
      (node (ref "U1") (pin "10") (pinfunction "PD6(AIN0)_10") (pintype "bidirectional"))
    )
    (net (code "3") (name "/CHG_POL") (class "Default")
      (node (ref "R30") (pin "1") (pinfunction "1_1") (pintype "passive"))
      (node (ref "U1") (pin "11") (pinfunction "PD7(AIN1)_11") (pintype "bidirectional"))
    )
    (net (code "4") (name "/CS") (class "Default")
      (node (ref "J6") (pin "7") (pinfunction "CS_7") (pintype "bidirectional"))
      (node (ref "R29") (pin "2") (pinfunction "2_2") (pintype "passive"))
      (node (ref "R66") (pin "2") (pinfunction "2_2") (pintype "passive"))
    )
    (net (code "5") (name "/D0") (class "Default")
      (node (ref "J6") (pin "3") (pinfunction "D0_3") (pintype "bidirectional"))
      (node (ref "R14") (pin "2") (pinfunction "2_2") (pintype "passive"))
    )
    (net (code "6") (name "/D1") (class "Default")
      (node (ref "J6") (pin "4") (pinfunction "D1_4") (pintype "bidirectional"))
      (node (ref "R17") (pin "2") (pinfunction "2_2") (pintype "passive"))
    )
    (net (code "7") (name "/DSP_RST") (class "Default")
      (node (ref "R21") (pin "1") (pinfunction "1_1") (pintype "passive"))
      (node (ref "U1") (pin "12") (pinfunction "PB0(ICP)_12") (pintype "bidirectional"))
    )
    (net (code "8") (name "/DTR") (class "Default")
      (node (ref "C33") (pin "2") (pinfunction "2_2") (pintype "passive"))
      (node (ref "J4") (pin "P$1") (pinfunction "DTR_P$1") (pintype "bidirectional"))
    )
    (net (code "9") (name "/EN_5V") (class "Default")
      (node (ref "R45") (pin "1") (pinfunction "1_1") (pintype "passive"))
      (node (ref "R46") (pin "2") (pinfunction "2_2") (pintype "passive"))
      (node (ref "U2") (pin "4") (pinfunction "EN_4") (pintype "bidirectional"))
    )
    (net (code "10") (name "/EN_TPS54531") (class "Default")
      (node (ref "Q4") (pin "3") (pinfunction "D_3") (pintype "passive"))
      (node (ref "R41") (pin "1") (pinfunction "1_1") (pintype "passive"))
      (node (ref "U8") (pin "3") (pinfunction "EN_3") (pintype "bidirectional"))
    )
    (net (code "11") (name "/ISENSE") (class "Default")
      (node (ref "TP4") (pin "1") (pinfunction "1_1") (pintype "passive"))
      (node (ref "U1") (pin "22") (pinfunction "ADC7_22") (pintype "bidirectional"))
      (node (ref "U4") (pin "3") (pinfunction "OUT_3") (pintype "output"))
      (node (ref "U6") (pin "13") (pinfunction "I_13") (pintype "input"))
    )
    (net (code "12") (name "/MISO") (class "Default")
      (node (ref "J3") (pin "1") (pinfunction "1_1") (pintype "passive"))
      (node (ref "R24") (pin "1") (pinfunction "1_1") (pintype "passive"))
      (node (ref "U1") (pin "16") (pinfunction "PB4(MISO)_16") (pintype "bidirectional"))
    )
    (net (code "13") (name "/MOSI") (class "Default")
      (node (ref "J3") (pin "4") (pinfunction "4_4") (pintype "passive"))
      (node (ref "R17") (pin "1") (pinfunction "1_1") (pintype "passive"))
      (node (ref "U1") (pin "15") (pinfunction "PB3(MOSI/OC2)_15") (pintype "bidirectional"))
    )
    (net (code "14") (name "/N$31") (class "Default")
      (node (ref "OP1") (pin "4") (pinfunction "COL_4") (pintype "passive"))
      (node (ref "R19") (pin "1") (pinfunction "1_1") (pintype "passive"))
      (node (ref "R99") (pin "1") (pinfunction "1_1") (pintype "passive"))
      (node (ref "TP5") (pin "1") (pinfunction "1_1") (pintype "passive"))
    )
    (net (code "15") (name "/OVC_ALARM") (class "Default")
      (node (ref "TP10") (pin "1") (pinfunction "1_1") (pintype "passive"))
      (node (ref "U1") (pin "9") (pinfunction "PD5(T1)_9") (pintype "bidirectional"))
      (node (ref "U6") (pin "10") (pinfunction "O_10") (pintype "output"))
    )
    (net (code "16") (name "/PEDAL_IP") (class "Default")
      (node (ref "U1") (pin "32") (pinfunction "PD2(INT0)_32") (pintype "bidirectional"))
      (node (ref "U6") (pin "4") (pinfunction "O_4") (pintype "output"))
    )
    (net (code "17") (name "/PUSH") (class "Default")
      (node (ref "R65") (pin "1") (pinfunction "1_1") (pintype "passive"))
      (node (ref "TP9") (pin "1") (pinfunction "1_1") (pintype "passive"))
      (node (ref "U6") (pin "5") (pinfunction "I_5") (pintype "input"))
    )
    (net (code "18") (name "/PUSH_FILT") (class "Default")
      (node (ref "U1") (pin "25") (pinfunction "PC2(ADC2)_25") (pintype "bidirectional"))
      (node (ref "U6") (pin "8") (pinfunction "O_8") (pintype "output"))
    )
    (net (code "19") (name "/RESET") (class "Default")
      (node (ref "C33") (pin "1") (pinfunction "1_1") (pintype "passive"))
      (node (ref "J3") (pin "5") (pinfunction "5_5") (pintype "passive"))
      (node (ref "R77") (pin "1") (pinfunction "1_1") (pintype "passive"))
      (node (ref "U1") (pin "29") (pinfunction "PC6(/RESET)_29") (pintype "bidirectional"))
    )
    (net (code "20") (name "/ROTA") (class "Default")
      (node (ref "C23") (pin "2") (pinfunction "2_2") (pintype "passive"))
      (node (ref "R53") (pin "1") (pinfunction "1_1") (pintype "passive"))
      (node (ref "S1") (pin "A") (pinfunction "A_A") (pintype "bidirectional"))
      (node (ref "U3") (pin "5") (pinfunction "I_5") (pintype "input"))
    )
    (net (code "21") (name "/ROTA_FILT") (class "Default")
      (node (ref "U1") (pin "2") (pinfunction "PD4(XCK/T0)_2") (pintype "bidirectional"))
      (node (ref "U3") (pin "4") (pinfunction "O_4") (pintype "output"))
    )
    (net (code "22") (name "/ROTB") (class "Default")
      (node (ref "C22") (pin "2") (pinfunction "2_2") (pintype "passive"))
      (node (ref "R52") (pin "1") (pinfunction "1_1") (pintype "passive"))
      (node (ref "S1") (pin "B") (pinfunction "B_B") (pintype "bidirectional"))
      (node (ref "U3") (pin "11") (pinfunction "I_11") (pintype "input"))
    )
    (net (code "23") (name "/ROTB_FILT") (class "Default")
      (node (ref "U1") (pin "1") (pinfunction "PD3(INT1)_1") (pintype "bidirectional"))
      (node (ref "U3") (pin "8") (pinfunction "O_8") (pintype "output"))
    )
    (net (code "24") (name "/ROTPUSH") (class "Default")
      (node (ref "C24") (pin "2") (pinfunction "2_2") (pintype "passive"))
      (node (ref "R54") (pin "1") (pinfunction "1_1") (pintype "passive"))
      (node (ref "S1") (pin "SW+") (pinfunction "SW+_SW+") (pintype "bidirectional"))
      (node (ref "U3") (pin "1") (pinfunction "I_1") (pintype "input"))
    )
    (net (code "25") (name "/RPUSH_FILT") (class "Default")
      (node (ref "U1") (pin "26") (pinfunction "PC3(ADC3)_26") (pintype "bidirectional"))
      (node (ref "U3") (pin "12") (pinfunction "O_12") (pintype "output"))
    )
    (net (code "26") (name "/RST") (class "Default")
      (node (ref "J6") (pin "5") (pinfunction "RST_5") (pintype "bidirectional"))
      (node (ref "R21") (pin "2") (pinfunction "2_2") (pintype "passive"))
    )
    (net (code "27") (name "/RX-I") (class "Default")
      (node (ref "J4") (pin "P$3") (pinfunction "RXI_P$3") (pintype "bidirectional"))
      (node (ref "U1") (pin "30") (pinfunction "PD0(RXD)_30") (pintype "bidirectional"))
    )
    (net (code "28") (name "/SCK") (class "Default")
      (node (ref "J3") (pin "3") (pinfunction "3_3") (pintype "passive"))
      (node (ref "R14") (pin "1") (pinfunction "1_1") (pintype "passive"))
      (node (ref "U1") (pin "17") (pinfunction "PB5(SCK)_17") (pintype "bidirectional"))
    )
    (net (code "29") (name "/SCL") (class "Default")
      (node (ref "L5") (pin "2") (pinfunction "2_2") (pintype "passive"))
      (node (ref "R57") (pin "1") (pinfunction "1_1") (pintype "passive"))
      (node (ref "TP7") (pin "1") (pinfunction "1_1") (pintype "passive"))
      (node (ref "U1") (pin "28") (pinfunction "PC5(ADC5/SCL)_28") (pintype "bidirectional"))
    )
    (net (code "30") (name "/SDA") (class "Default")
      (node (ref "L6") (pin "2") (pinfunction "2_2") (pintype "passive"))
      (node (ref "R58") (pin "1") (pinfunction "1_1") (pintype "passive"))
      (node (ref "TP6") (pin "1") (pinfunction "1_1") (pintype "passive"))
      (node (ref "U1") (pin "27") (pinfunction "PC4(ADC4/SDA)_27") (pintype "bidirectional"))
    )
    (net (code "31") (name "/SPARE") (class "Default")
      (node (ref "C9") (pin "1") (pinfunction "1_1") (pintype "passive"))
      (node (ref "R18") (pin "2") (pinfunction "2_2") (pintype "passive"))
      (node (ref "R99") (pin "2") (pinfunction "2_2") (pintype "passive"))
      (node (ref "U1") (pin "23") (pinfunction "PC0(ADC0)_23") (pintype "bidirectional"))
      (node (ref "U6") (pin "1") (pinfunction "I_1") (pintype "input"))
    )
    (net (code "32") (name "/SS") (class "Default")
      (node (ref "R29") (pin "1") (pinfunction "1_1") (pintype "passive"))
      (node (ref "U1") (pin "14") (pinfunction "PB2(SS/OC1B)_14") (pintype "bidirectional"))
    )
    (net (code "33") (name "/TEST") (class "Default")
      (node (ref "Q1") (pin "1") (pinfunction "G_1") (pintype "passive"))
      (node (ref "R27") (pin "2") (pinfunction "2_2") (pintype "passive"))
      (node (ref "R34") (pin "2") (pinfunction "2_2") (pintype "passive"))
      (node (ref "TP13") (pin "1") (pinfunction "1_1") (pintype "passive"))
    )
    (net (code "34") (name "/TX-O") (class "Default")
      (node (ref "J4") (pin "P$2") (pinfunction "TXO_P$2") (pintype "bidirectional"))
      (node (ref "U1") (pin "31") (pinfunction "PD1(TXD)_31") (pintype "bidirectional"))
    )
    (net (code "35") (name "/VOSEN") (class "Default")
      (node (ref "C13") (pin "2") (pinfunction "2_2") (pintype "passive"))
      (node (ref "D2") (pin "3") (pinfunction "AC_3") (pintype "passive"))
      (node (ref "R36") (pin "1") (pinfunction "1_1") (pintype "passive"))
      (node (ref "R37") (pin "2") (pinfunction "2_2") (pintype "passive"))
      (node (ref "TP3") (pin "1") (pinfunction "1_1") (pintype "passive"))
      (node (ref "U1") (pin "19") (pinfunction "ADC6_19") (pintype "bidirectional"))
    )
    (net (code "36") (name "/VOUT") (class "Default")
      (node (ref "D8") (pin "C") (pinfunction "K_C") (pintype "bidirectional"))
      (node (ref "J2") (pin "1") (pinfunction "1_1") (pintype "passive"))
      (node (ref "K1") (pin "4") (pinfunction "S_4") (pintype "passive"))
      (node (ref "K1") (pin "6") (pinfunction "P_6") (pintype "passive"))
      (node (ref "K1") (pin "7") (pinfunction "O_7") (pintype "passive"))
      (node (ref "R1") (pin "2") (pinfunction "2_2") (pintype "passive"))
      (node (ref "R12") (pin "2") (pinfunction "2_2") (pintype "passive"))
      (node (ref "R37") (pin "1") (pinfunction "1_1") (pintype "passive"))
      (node (ref "TP11") (pin "1") (pinfunction "1_1") (pintype "passive"))
    )
    (net (code "37") (name "/VO_TPS") (class "Default")
      (node (ref "C19") (pin "2") (pinfunction "2_2") (pintype "passive"))
      (node (ref "C34") (pin "2") (pinfunction "2_2") (pintype "passive"))
      (node (ref "C39") (pin "1") (pinfunction "1_1") (pintype "passive"))
      (node (ref "C40") (pin "1") (pinfunction "1_1") (pintype "passive"))
      (node (ref "C41") (pin "1") (pinfunction "1_1") (pintype "passive"))
      (node (ref "C42") (pin "1") (pinfunction "1_1") (pintype "passive"))
      (node (ref "C43") (pin "1") (pinfunction "1_1") (pintype "passive"))
      (node (ref "L2") (pin "2") (pinfunction "2_2") (pintype "passive"))
      (node (ref "R11") (pin "2") (pinfunction "2_2") (pintype "passive"))
      (node (ref "R12") (pin "1") (pinfunction "1_1") (pintype "passive"))
      (node (ref "TP14") (pin "1") (pinfunction "1_1") (pintype "passive"))
      (node (ref "U4") (pin "5") (pinfunction "RS+_5") (pintype "power_in"))
    )
    (net (code "38") (name "/VRELAY") (class "Default")
      (node (ref "D3") (pin "3") (pinfunction "AC_3") (pintype "passive"))
      (node (ref "K1") (pin "8") (pinfunction "-_8") (pintype "passive"))
      (node (ref "Q3") (pin "3") (pinfunction "D_3") (pintype "passive"))
      (node (ref "TP8") (pin "1") (pinfunction "1_1") (pintype "passive"))
    )
    (net (code "39") (name "5VMCU") (class "Default")
      (node (ref "C1") (pin "2") (pinfunction "2_2") (pintype "passive"))
      (node (ref "C12") (pin "2") (pinfunction "2_2") (pintype "passive"))
      (node (ref "C15") (pin "2") (pinfunction "2_2") (pintype "passive"))
      (node (ref "C2") (pin "2") (pinfunction "2_2") (pintype "passive"))
      (node (ref "C20") (pin "2") (pinfunction "2_2") (pintype "passive"))
      (node (ref "C25") (pin "2") (pinfunction "2_2") (pintype "passive"))
      (node (ref "C26") (pin "1") (pinfunction "1_1") (pintype "passive"))
      (node (ref "C31") (pin "2") (pinfunction "2_2") (pintype "passive"))
      (node (ref "C4") (pin "1") (pinfunction "1_1") (pintype "passive"))
      (node (ref "C44") (pin "2") (pinfunction "2_2") (pintype "passive"))
      (node (ref "C45") (pin "2") (pinfunction "2_2") (pintype "passive"))
      (node (ref "C46") (pin "2") (pinfunction "2_2") (pintype "passive"))
      (node (ref "C5") (pin "2") (pinfunction "2_2") (pintype "passive"))
      (node (ref "C50") (pin "2") (pinfunction "2_2") (pintype "passive"))
      (node (ref "C51") (pin "2") (pinfunction "2_2") (pintype "passive"))
      (node (ref "C52") (pin "1") (pinfunction "1_1") (pintype "passive"))
      (node (ref "C53") (pin "2") (pinfunction "2_2") (pintype "passive"))
      (node (ref "D2") (pin "2") (pinfunction "C_2") (pintype "passive"))
      (node (ref "D3") (pin "2") (pinfunction "C_2") (pintype "passive"))
      (node (ref "D4") (pin "2") (pinfunction "C_2") (pintype "passive"))
      (node (ref "J3") (pin "2") (pinfunction "2_2") (pintype "passive"))
      (node (ref "J4") (pin "P$4") (pinfunction "VCC_P$4") (pintype "bidirectional"))
      (node (ref "J6") (pin "2") (pinfunction "VCC_2") (pintype "bidirectional"))
      (node (ref "K1") (pin "1") (pinfunction "+_1") (pintype "passive"))
      (node (ref "L1") (pin "2") (pinfunction "2_2") (pintype "passive"))
      (node (ref "R13") (pin "2") (pinfunction "2_2") (pintype "passive"))
      (node (ref "R15") (pin "1") (pinfunction "1_1") (pintype "passive"))
      (node (ref "R19") (pin "2") (pinfunction "2_2") (pintype "passive"))
      (node (ref "R35") (pin "1") (pinfunction "1_1") (pintype "passive"))
      (node (ref "R38") (pin "1") (pinfunction "1_1") (pintype "passive"))
      (node (ref "R40") (pin "1") (pinfunction "1_1") (pintype "passive"))
      (node (ref "R52") (pin "2") (pinfunction "2_2") (pintype "passive"))
      (node (ref "R53") (pin "2") (pinfunction "2_2") (pintype "passive"))
      (node (ref "R54") (pin "2") (pinfunction "2_2") (pintype "passive"))
      (node (ref "R57") (pin "2") (pinfunction "2_2") (pintype "passive"))
      (node (ref "R58") (pin "2") (pinfunction "2_2") (pintype "passive"))
      (node (ref "R66") (pin "1") (pinfunction "1_1") (pintype "passive"))
      (node (ref "R77") (pin "2") (pinfunction "2_2") (pintype "passive"))
      (node (ref "U1") (pin "18") (pinfunction "AVCC_18") (pintype "bidirectional"))
      (node (ref "U1") (pin "4") (pinfunction "VCC_4") (pintype "bidirectional"))
      (node (ref "U1") (pin "6") (pinfunction "VCC_6") (pintype "bidirectional"))
      (node (ref "U3") (pin "14") (pinfunction "VCC_14") (pintype "power_in"))
      (node (ref "U6") (pin "14") (pinfunction "VCC_14") (pintype "power_in"))
      (node (ref "U7") (pin "1") (pinfunction "VCC_1") (pintype "bidirectional"))
    )
    (net (code "40") (name "EN_DCDC") (class "Default")
      (node (ref "Q4") (pin "1") (pinfunction "G_1") (pintype "passive"))
      (node (ref "R31") (pin "1") (pinfunction "1_1") (pintype "passive"))
      (node (ref "R42") (pin "2") (pinfunction "2_2") (pintype "passive"))
      (node (ref "U1") (pin "24") (pinfunction "PC1(ADC1)_24") (pintype "bidirectional"))
    )
    (net (code "41") (name "GND") (class "Default")
      (node (ref "C1") (pin "1") (pinfunction "1_1") (pintype "passive"))
      (node (ref "C10") (pin "1") (pinfunction "1_1") (pintype "passive"))
      (node (ref "C11") (pin "1") (pinfunction "1_1") (pintype "passive"))
      (node (ref "C12") (pin "1") (pinfunction "1_1") (pintype "passive"))
      (node (ref "C13") (pin "1") (pinfunction "1_1") (pintype "passive"))
      (node (ref "C14") (pin "1") (pinfunction "1_1") (pintype "passive"))
      (node (ref "C15") (pin "1") (pinfunction "1_1") (pintype "passive"))
      (node (ref "C16") (pin "1") (pinfunction "1_1") (pintype "passive"))
      (node (ref "C17") (pin "2") (pinfunction "2_2") (pintype "passive"))
      (node (ref "C18") (pin "2") (pinfunction "2_2") (pintype "passive"))
      (node (ref "C2") (pin "1") (pinfunction "1_1") (pintype "passive"))
      (node (ref "C20") (pin "1") (pinfunction "1_1") (pintype "passive"))
      (node (ref "C21") (pin "2") (pinfunction "2_2") (pintype "passive"))
      (node (ref "C22") (pin "1") (pinfunction "1_1") (pintype "passive"))
      (node (ref "C23") (pin "1") (pinfunction "1_1") (pintype "passive"))
      (node (ref "C24") (pin "1") (pinfunction "1_1") (pintype "passive"))
      (node (ref "C25") (pin "1") (pinfunction "1_1") (pintype "passive"))
      (node (ref "C26") (pin "2") (pinfunction "2_2") (pintype "passive"))
      (node (ref "C27") (pin "1") (pinfunction "1_1") (pintype "passive"))
      (node (ref "C28") (pin "1") (pinfunction "1_1") (pintype "passive"))
      (node (ref "C30") (pin "1") (pinfunction "1_1") (pintype "passive"))
      (node (ref "C31") (pin "1") (pinfunction "1_1") (pintype "passive"))
      (node (ref "C32") (pin "1") (pinfunction "1_1") (pintype "passive"))
      (node (ref "C34") (pin "1") (pinfunction "1_1") (pintype "passive"))
      (node (ref "C35") (pin "2") (pinfunction "2_2") (pintype "passive"))
      (node (ref "C36") (pin "1") (pinfunction "1_1") (pintype "passive"))
      (node (ref "C38") (pin "1") (pinfunction "1_1") (pintype "passive"))
      (node (ref "C39") (pin "2") (pinfunction "2_2") (pintype "passive"))
      (node (ref "C4") (pin "2") (pinfunction "2_2") (pintype "passive"))
      (node (ref "C40") (pin "2") (pinfunction "2_2") (pintype "passive"))
      (node (ref "C41") (pin "2") (pinfunction "2_2") (pintype "passive"))
      (node (ref "C42") (pin "2") (pinfunction "2_2") (pintype "passive"))
      (node (ref "C44") (pin "1") (pinfunction "1_1") (pintype "passive"))
      (node (ref "C45") (pin "1") (pinfunction "1_1") (pintype "passive"))
      (node (ref "C46") (pin "1") (pinfunction "1_1") (pintype "passive"))
      (node (ref "C47") (pin "1") (pinfunction "1_1") (pintype "passive"))
      (node (ref "C48") (pin "1") (pinfunction "1_1") (pintype "passive"))
      (node (ref "C49") (pin "1") (pinfunction "1_1") (pintype "passive"))
      (node (ref "C50") (pin "1") (pinfunction "1_1") (pintype "passive"))
      (node (ref "C51") (pin "1") (pinfunction "1_1") (pintype "passive"))
      (node (ref "C52") (pin "2") (pinfunction "2_2") (pintype "passive"))
      (node (ref "C53") (pin "1") (pinfunction "1_1") (pintype "passive"))
      (node (ref "C54") (pin "1") (pinfunction "1_1") (pintype "passive"))
      (node (ref "C6") (pin "2") (pinfunction "2_2") (pintype "passive"))
      (node (ref "C7") (pin "1") (pinfunction "1_1") (pintype "passive"))
      (node (ref "C8") (pin "1") (pinfunction "1_1") (pintype "passive"))
      (node (ref "C9") (pin "2") (pinfunction "2_2") (pintype "passive"))
      (node (ref "D1") (pin "+") (pinfunction "A_+") (pintype "bidirectional"))
      (node (ref "D2") (pin "1") (pinfunction "A_1") (pintype "passive"))
      (node (ref "D4") (pin "1") (pinfunction "A_1") (pintype "passive"))
      (node (ref "D6") (pin "1") (pinfunction "A_1") (pintype "bidirectional"))
      (node (ref "D8") (pin "A") (pinfunction "A_A") (pintype "bidirectional"))
      (node (ref "J1") (pin "1") (pinfunction "1_1") (pintype "passive"))
      (node (ref "J2") (pin "2") (pinfunction "2_2") (pintype "passive"))
      (node (ref "J3") (pin "6") (pinfunction "6_6") (pintype "passive"))
      (node (ref "J4") (pin "P$5") (pinfunction "CTS_P$5") (pintype "bidirectional"))
      (node (ref "J4") (pin "P$6") (pinfunction "GND_P$6") (pintype "bidirectional"))
      (node (ref "J6") (pin "1") (pinfunction "GND_1") (pintype "bidirectional"))
      (node (ref "K1") (pin "2") (pinfunction "O_2") (pintype "passive"))
      (node (ref "K1") (pin "3") (pinfunction "P_3") (pintype "passive"))
      (node (ref "K1") (pin "5") (pinfunction "S_5") (pintype "passive"))
      (node (ref "OP1") (pin "3") (pinfunction "EMIT_3") (pintype "passive"))
      (node (ref "Q1") (pin "2") (pinfunction "S_2") (pintype "passive"))
      (node (ref "Q2") (pin "2") (pinfunction "S_2") (pintype "passive"))
      (node (ref "Q3") (pin "2") (pinfunction "S_2") (pintype "passive"))
      (node (ref "Q9") (pin "2") (pinfunction "S_2") (pintype "passive"))
      (node (ref "R16") (pin "2") (pinfunction "2_2") (pintype "passive"))
      (node (ref "R18") (pin "1") (pinfunction "1_1") (pintype "passive"))
      (node (ref "R22") (pin "2") (pinfunction "2_2") (pintype "passive"))
      (node (ref "R32") (pin "2") (pinfunction "2_2") (pintype "passive"))
      (node (ref "R34") (pin "1") (pinfunction "1_1") (pintype "passive"))
      (node (ref "R36") (pin "2") (pinfunction "2_2") (pintype "passive"))
      (node (ref "R42") (pin "1") (pinfunction "1_1") (pintype "passive"))
      (node (ref "R43") (pin "1") (pinfunction "1_1") (pintype "passive"))
      (node (ref "R44") (pin "1") (pinfunction "1_1") (pintype "passive"))
      (node (ref "R46") (pin "1") (pinfunction "1_1") (pintype "passive"))
      (node (ref "S1") (pin "C") (pinfunction "C_C") (pintype "bidirectional"))
      (node (ref "S1") (pin "SW-") (pinfunction "SW-_SW-") (pintype "bidirectional"))
      (node (ref "S2") (pin "2") (pinfunction "2_2") (pintype "passive"))
      (node (ref "TP1") (pin "1") (pinfunction "1_1") (pintype "passive"))
      (node (ref "TP12") (pin "1") (pinfunction "1_1") (pintype "passive"))
      (node (ref "U1") (pin "21") (pinfunction "GND_21") (pintype "bidirectional"))
      (node (ref "U1") (pin "3") (pinfunction "GND_3") (pintype "bidirectional"))
      (node (ref "U1") (pin "5") (pinfunction "AGND_5") (pintype "bidirectional"))
      (node (ref "U2") (pin "2") (pinfunction "GND_2") (pintype "bidirectional"))
      (node (ref "U3") (pin "7") (pinfunction "GND_7") (pintype "power_in"))
      (node (ref "U4") (pin "1") (pinfunction "GND_1") (pintype "passive"))
      (node (ref "U4") (pin "2") (pinfunction "GND_2_2") (pintype "passive"))
      (node (ref "U5") (pin "3") (pinfunction "GND_3") (pintype "bidirectional"))
      (node (ref "U6") (pin "7") (pinfunction "GND_7") (pintype "power_in"))
      (node (ref "U7") (pin "10") (pinfunction "A1_10") (pintype "bidirectional"))
      (node (ref "U7") (pin "16") (pinfunction "GND_16") (pintype "bidirectional"))
      (node (ref "U7") (pin "7") (pinfunction "A2_7") (pintype "bidirectional"))
      (node (ref "U7") (pin "8") (pinfunction "~{G}_8") (pintype "bidirectional"))
      (node (ref "U7") (pin "9") (pinfunction "A0_9") (pintype "bidirectional"))
      (node (ref "U8") (pin "7") (pinfunction "GND_7") (pintype "bidirectional"))
      (node (ref "U8") (pin "PAD") (pinfunction "PAD_PAD") (pintype "bidirectional"))
      (node (ref "X1") (pin "2") (pinfunction "2_2") (pintype "passive"))
    )
    (net (code "42") (name "Net-(BZ1-+)") (class "Default")
      (node (ref "BZ1") (pin "1") (pinfunction "+_1") (pintype "passive"))
      (node (ref "C27") (pin "2") (pinfunction "2_2") (pintype "passive"))
      (node (ref "L7") (pin "2") (pinfunction "2_2") (pintype "passive"))
      (node (ref "R61") (pin "2") (pinfunction "2_2") (pintype "passive"))
    )
    (net (code "43") (name "Net-(BZ1--)") (class "Default")
      (node (ref "BZ1") (pin "2") (pinfunction "-_2") (pintype "passive"))
      (node (ref "Q9") (pin "3") (pinfunction "D_3") (pintype "passive"))
      (node (ref "R61") (pin "1") (pinfunction "1_1") (pintype "passive"))
    )
    (net (code "44") (name "Net-(C10-Pad2)") (class "Default")
      (node (ref "C10") (pin "2") (pinfunction "2_2") (pintype "passive"))
      (node (ref "R13") (pin "1") (pinfunction "1_1") (pintype "passive"))
      (node (ref "R65") (pin "2") (pinfunction "2_2") (pintype "passive"))
      (node (ref "S2") (pin "4") (pinfunction "4_4") (pintype "passive"))
    )
    (net (code "45") (name "Net-(C36-Pad2)") (class "Default")
      (node (ref "C36") (pin "2") (pinfunction "2_2") (pintype "passive"))
      (node (ref "J1") (pin "2") (pinfunction "2_2") (pintype "passive"))
      (node (ref "PTC1") (pin "2") (pinfunction "2_2") (pintype "passive"))
    )
    (net (code "46") (name "Net-(C37-Pad1)") (class "Default")
      (node (ref "C37") (pin "1") (pinfunction "1_1") (pintype "passive"))
      (node (ref "R44") (pin "2") (pinfunction "2_2") (pintype "passive"))
    )
    (net (code "47") (name "Net-(D1-K)") (class "Default")
      (node (ref "C3") (pin "2") (pinfunction "2_2") (pintype "passive"))
      (node (ref "D1") (pin "-") (pinfunction "K_-") (pintype "bidirectional"))
      (node (ref "L1") (pin "1") (pinfunction "1_1") (pintype "passive"))
      (node (ref "U2") (pin "6") (pinfunction "LX_6") (pintype "bidirectional"))
    )
    (net (code "48") (name "Net-(D5-A)") (class "Default")
      (node (ref "D5") (pin "1") (pinfunction "A_1") (pintype "bidirectional"))
      (node (ref "PTC1") (pin "1") (pinfunction "1_1") (pintype "passive"))
    )
    (net (code "49") (name "Net-(D6-K)") (class "Default")
      (node (ref "C29") (pin "2") (pinfunction "2_2") (pintype "passive"))
      (node (ref "D6") (pin "2") (pinfunction "K_2") (pintype "bidirectional"))
      (node (ref "L2") (pin "1") (pinfunction "1_1") (pintype "passive"))
      (node (ref "U8") (pin "8") (pinfunction "PH_8") (pintype "bidirectional"))
    )
    (net (code "50") (name "Net-(J5-Pad1)") (class "Default")
      (node (ref "J5") (pin "1") (pinfunction "1_1") (pintype "passive"))
      (node (ref "L3") (pin "1") (pinfunction "1_1") (pintype "passive"))
    )
    (net (code "51") (name "Net-(J5-Pad2)") (class "Default")
      (node (ref "J5") (pin "2") (pinfunction "2_2") (pintype "passive"))
      (node (ref "L4") (pin "1") (pinfunction "1_1") (pintype "passive"))
    )
    (net (code "52") (name "Net-(J6-DC)") (class "Default")
      (node (ref "J6") (pin "6") (pinfunction "DC_6") (pintype "bidirectional"))
      (node (ref "R24") (pin "2") (pinfunction "2_2") (pintype "passive"))
    )
    (net (code "53") (name "Net-(L3-Pad2)") (class "Default")
      (node (ref "L3") (pin "2") (pinfunction "2_2") (pintype "passive"))
      (node (ref "R26") (pin "1") (pinfunction "1_1") (pintype "passive"))
    )
    (net (code "54") (name "Net-(L4-Pad2)") (class "Default")
      (node (ref "L4") (pin "2") (pinfunction "2_2") (pintype "passive"))
      (node (ref "R22") (pin "1") (pinfunction "1_1") (pintype "passive"))
    )
    (net (code "55") (name "Net-(LED1-C)") (class "Default")
      (node (ref "LED1") (pin "K") (pinfunction "C_K") (pintype "passive"))
      (node (ref "Q2") (pin "3") (pinfunction "D_3") (pintype "passive"))
    )
    (net (code "56") (name "Net-(LED1-PadA)") (class "Default")
      (node (ref "LED1") (pin "A") (pinfunction "A_A") (pintype "passive"))
      (node (ref "R35") (pin "2") (pinfunction "2_2") (pintype "passive"))
    )
    (net (code "57") (name "Net-(LED2-C)") (class "Default")
      (node (ref "LED2") (pin "K") (pinfunction "C_K") (pintype "passive"))
      (node (ref "LED3") (pin "K") (pinfunction "C_K") (pintype "passive"))
      (node (ref "Q1") (pin "3") (pinfunction "D_3") (pintype "passive"))
    )
    (net (code "58") (name "Net-(LED2-PadA)") (class "Default")
      (node (ref "LED2") (pin "A") (pinfunction "A_A") (pintype "passive"))
      (node (ref "R38") (pin "2") (pinfunction "2_2") (pintype "passive"))
    )
    (net (code "59") (name "Net-(LED3-PadA)") (class "Default")
      (node (ref "LED3") (pin "A") (pinfunction "A_A") (pintype "passive"))
      (node (ref "R40") (pin "2") (pinfunction "2_2") (pintype "passive"))
    )
    (net (code "60") (name "Net-(OP1-C)") (class "Default")
      (node (ref "OP1") (pin "2") (pinfunction "C_2") (pintype "passive"))
      (node (ref "R26") (pin "2") (pinfunction "2_2") (pintype "passive"))
    )
    (net (code "61") (name "Net-(Q2-G)") (class "Default")
      (node (ref "Q2") (pin "1") (pinfunction "G_1") (pintype "passive"))
      (node (ref "R31") (pin "2") (pinfunction "2_2") (pintype "passive"))
    )
    (net (code "62") (name "Net-(Q3-G)") (class "Default")
      (node (ref "Q3") (pin "1") (pinfunction "G_1") (pintype "passive"))
      (node (ref "R30") (pin "2") (pinfunction "2_2") (pintype "passive"))
    )
    (net (code "63") (name "Net-(Q4-S)") (class "Default")
      (node (ref "Q4") (pin "2") (pinfunction "S_2") (pintype "passive"))
      (node (ref "R43") (pin "2") (pinfunction "2_2") (pintype "passive"))
    )
    (net (code "64") (name "Net-(Q9-G)") (class "Default")
      (node (ref "Q9") (pin "1") (pinfunction "G_1") (pintype "passive"))
      (node (ref "R28") (pin "2") (pinfunction "2_2") (pintype "passive"))
      (node (ref "R32") (pin "1") (pinfunction "1_1") (pintype "passive"))
    )
    (net (code "65") (name "Net-(U1-PB1(OC1A))") (class "Default")
      (node (ref "R27") (pin "1") (pinfunction "1_1") (pintype "passive"))
      (node (ref "U1") (pin "13") (pinfunction "PB1(OC1A)_13") (pintype "bidirectional"))
    )
    (net (code "66") (name "Net-(U1-PB6(XTAL1{slash}TOSC1))") (class "Default")
      (node (ref "U1") (pin "7") (pinfunction "PB6(XTAL1/TOSC1)_7") (pintype "bidirectional"))
      (node (ref "X1") (pin "3") (pinfunction "3_3") (pintype "passive"))
    )
    (net (code "67") (name "Net-(U1-PB7(XTAL2{slash}TOSC2))") (class "Default")
      (node (ref "U1") (pin "8") (pinfunction "PB7(XTAL2/TOSC2)_8") (pintype "bidirectional"))
      (node (ref "X1") (pin "1") (pinfunction "1_1") (pintype "passive"))
    )
    (net (code "68") (name "Net-(U2-BST)") (class "Default")
      (node (ref "C3") (pin "1") (pinfunction "1_1") (pintype "passive"))
      (node (ref "U2") (pin "1") (pinfunction "BST_1") (pintype "bidirectional"))
    )
    (net (code "69") (name "Net-(U2-FB)") (class "Default")
      (node (ref "C5") (pin "1") (pinfunction "1_1") (pintype "passive"))
      (node (ref "R15") (pin "2") (pinfunction "2_2") (pintype "passive"))
      (node (ref "R16") (pin "1") (pinfunction "1_1") (pintype "passive"))
      (node (ref "U2") (pin "3") (pinfunction "FB_3") (pintype "bidirectional"))
    )
    (net (code "70") (name "Net-(U3A-I)") (class "Default")
      (node (ref "C49") (pin "2") (pinfunction "2_2") (pintype "passive"))
      (node (ref "R25") (pin "2") (pinfunction "2_2") (pintype "passive"))
      (node (ref "U3") (pin "13") (pinfunction "I_13") (pintype "input"))
    )
    (net (code "71") (name "Net-(U3B-O)") (class "Default")
      (node (ref "R2") (pin "1") (pinfunction "1_1") (pintype "passive"))
      (node (ref "U3") (pin "10") (pinfunction "O_10") (pintype "output"))
    )
    (net (code "72") (name "Net-(U3C-I)") (class "Default")
      (node (ref "C47") (pin "2") (pinfunction "2_2") (pintype "passive"))
      (node (ref "R2") (pin "2") (pinfunction "2_2") (pintype "passive"))
      (node (ref "U3") (pin "9") (pinfunction "I_9") (pintype "input"))
    )
    (net (code "73") (name "Net-(U3D-O)") (class "Default")
      (node (ref "R25") (pin "1") (pinfunction "1_1") (pintype "passive"))
      (node (ref "U3") (pin "2") (pinfunction "O_2") (pintype "output"))
    )
    (net (code "74") (name "Net-(U3E-I)") (class "Default")
      (node (ref "C48") (pin "2") (pinfunction "2_2") (pintype "passive"))
      (node (ref "R20") (pin "2") (pinfunction "2_2") (pintype "passive"))
      (node (ref "U3") (pin "3") (pinfunction "I_3") (pintype "input"))
    )
    (net (code "75") (name "Net-(U3F-O)") (class "Default")
      (node (ref "R20") (pin "1") (pinfunction "1_1") (pintype "passive"))
      (node (ref "U3") (pin "6") (pinfunction "O_6") (pintype "output"))
    )
    (net (code "76") (name "Net-(U4-RS-)") (class "Default")
      (node (ref "C43") (pin "2") (pinfunction "2_2") (pintype "passive"))
      (node (ref "R1") (pin "1") (pinfunction "1_1") (pintype "passive"))
      (node (ref "U4") (pin "4") (pinfunction "RS-_4") (pintype "input"))
    )
    (net (code "77") (name "Net-(U6A-O)") (class "Default")
      (node (ref "R39") (pin "1") (pinfunction "1_1") (pintype "passive"))
      (node (ref "U6") (pin "12") (pinfunction "O_12") (pintype "output"))
    )
    (net (code "78") (name "Net-(U6B-I)") (class "Default")
      (node (ref "C54") (pin "2") (pinfunction "2_2") (pintype "passive"))
      (node (ref "R39") (pin "2") (pinfunction "2_2") (pintype "passive"))
      (node (ref "U6") (pin "11") (pinfunction "I_11") (pintype "input"))
    )
    (net (code "79") (name "Net-(U6C-I)") (class "Default")
      (node (ref "C14") (pin "2") (pinfunction "2_2") (pintype "passive"))
      (node (ref "R33") (pin "2") (pinfunction "2_2") (pintype "passive"))
      (node (ref "U6") (pin "9") (pinfunction "I_9") (pintype "input"))
    )
    (net (code "80") (name "Net-(U6D-O)") (class "Default")
      (node (ref "R23") (pin "1") (pinfunction "1_1") (pintype "passive"))
      (node (ref "U6") (pin "2") (pinfunction "O_2") (pintype "output"))
    )
    (net (code "81") (name "Net-(U6E-I)") (class "Default")
      (node (ref "C11") (pin "2") (pinfunction "2_2") (pintype "passive"))
      (node (ref "R23") (pin "2") (pinfunction "2_2") (pintype "passive"))
      (node (ref "U6") (pin "3") (pinfunction "I_3") (pintype "input"))
    )
    (net (code "82") (name "Net-(U6F-O)") (class "Default")
      (node (ref "R33") (pin "1") (pinfunction "1_1") (pintype "passive"))
      (node (ref "U6") (pin "6") (pinfunction "O_6") (pintype "output"))
    )
    (net (code "83") (name "Net-(U7-DRAIN0)") (class "Default")
      (node (ref "R6") (pin "1") (pinfunction "1_1") (pintype "passive"))
      (node (ref "U7") (pin "3") (pinfunction "DRAIN0_3") (pintype "bidirectional"))
    )
    (net (code "84") (name "Net-(U7-DRAIN1)") (class "Default")
      (node (ref "R5") (pin "1") (pinfunction "1_1") (pintype "passive"))
      (node (ref "U7") (pin "4") (pinfunction "DRAIN1_4") (pintype "bidirectional"))
    )
    (net (code "85") (name "Net-(U7-DRAIN2)") (class "Default")
      (node (ref "R4") (pin "1") (pinfunction "1_1") (pintype "passive"))
      (node (ref "U7") (pin "5") (pinfunction "DRAIN2_5") (pintype "bidirectional"))
    )
    (net (code "86") (name "Net-(U7-DRAIN3)") (class "Default")
      (node (ref "R3") (pin "1") (pinfunction "1_1") (pintype "passive"))
      (node (ref "U7") (pin "6") (pinfunction "DRAIN3_6") (pintype "bidirectional"))
    )
    (net (code "87") (name "Net-(U7-DRAIN4)") (class "Default")
      (node (ref "R10") (pin "1") (pinfunction "1_1") (pintype "passive"))
      (node (ref "U7") (pin "11") (pinfunction "DRAIN4_11") (pintype "bidirectional"))
    )
    (net (code "88") (name "Net-(U7-DRAIN5)") (class "Default")
      (node (ref "R9") (pin "1") (pinfunction "1_1") (pintype "passive"))
      (node (ref "U7") (pin "12") (pinfunction "DRAIN5_12") (pintype "bidirectional"))
    )
    (net (code "89") (name "Net-(U7-DRAIN6)") (class "Default")
      (node (ref "R8") (pin "1") (pinfunction "1_1") (pintype "passive"))
      (node (ref "U7") (pin "13") (pinfunction "DRAIN6_13") (pintype "bidirectional"))
    )
    (net (code "90") (name "Net-(U7-DRAIN7)") (class "Default")
      (node (ref "R7") (pin "1") (pinfunction "1_1") (pintype "passive"))
      (node (ref "U7") (pin "14") (pinfunction "DRAIN7_14") (pintype "bidirectional"))
    )
    (net (code "91") (name "Net-(U7-SCL)") (class "Default")
      (node (ref "L5") (pin "1") (pinfunction "1_1") (pintype "passive"))
      (node (ref "U7") (pin "15") (pinfunction "SCL_15") (pintype "bidirectional"))
    )
    (net (code "92") (name "Net-(U7-SDA)") (class "Default")
      (node (ref "L6") (pin "1") (pinfunction "1_1") (pintype "passive"))
      (node (ref "U7") (pin "2") (pinfunction "SDA_2") (pintype "bidirectional"))
    )
    (net (code "93") (name "Net-(U8-BOOT)") (class "Default")
      (node (ref "C29") (pin "1") (pinfunction "1_1") (pintype "passive"))
      (node (ref "U8") (pin "1") (pinfunction "BOOT_1") (pintype "bidirectional"))
    )
    (net (code "94") (name "Net-(U8-COMP)") (class "Default")
      (node (ref "C37") (pin "2") (pinfunction "2_2") (pintype "passive"))
      (node (ref "C38") (pin "2") (pinfunction "2_2") (pintype "passive"))
      (node (ref "U8") (pin "6") (pinfunction "COMP_6") (pintype "bidirectional"))
    )
    (net (code "95") (name "Net-(U8-SS)") (class "Default")
      (node (ref "C30") (pin "2") (pinfunction "2_2") (pintype "passive"))
      (node (ref "U8") (pin "4") (pinfunction "SS_4") (pintype "bidirectional"))
    )
    (net (code "96") (name "Net-(U8-VSENSE)") (class "Default")
      (node (ref "C19") (pin "1") (pinfunction "1_1") (pintype "passive"))
      (node (ref "R10") (pin "2") (pinfunction "2_2") (pintype "passive"))
      (node (ref "R11") (pin "1") (pinfunction "1_1") (pintype "passive"))
      (node (ref "R3") (pin "2") (pinfunction "2_2") (pintype "passive"))
      (node (ref "R4") (pin "2") (pinfunction "2_2") (pintype "passive"))
      (node (ref "R5") (pin "2") (pinfunction "2_2") (pintype "passive"))
      (node (ref "R6") (pin "2") (pinfunction "2_2") (pintype "passive"))
      (node (ref "R7") (pin "2") (pinfunction "2_2") (pintype "passive"))
      (node (ref "R8") (pin "2") (pinfunction "2_2") (pintype "passive"))
      (node (ref "R9") (pin "2") (pinfunction "2_2") (pintype "passive"))
      (node (ref "U8") (pin "5") (pinfunction "VSENSE_5") (pintype "bidirectional"))
    )
    (net (code "97") (name "VCC") (class "Default")
      (node (ref "C17") (pin "1") (pinfunction "1_1") (pintype "passive"))
      (node (ref "C18") (pin "1") (pinfunction "1_1") (pintype "passive"))
      (node (ref "C21") (pin "1") (pinfunction "1_1") (pintype "passive"))
      (node (ref "C28") (pin "2") (pinfunction "2_2") (pintype "passive"))
      (node (ref "C35") (pin "1") (pinfunction "1_1") (pintype "passive"))
      (node (ref "C6") (pin "1") (pinfunction "1_1") (pintype "passive"))
      (node (ref "C7") (pin "2") (pinfunction "2_2") (pintype "passive"))
      (node (ref "D5") (pin "2") (pinfunction "K_2") (pintype "bidirectional"))
      (node (ref "L7") (pin "1") (pinfunction "1_1") (pintype "passive"))
      (node (ref "R41") (pin "2") (pinfunction "2_2") (pintype "passive"))
      (node (ref "R45") (pin "2") (pinfunction "2_2") (pintype "passive"))
      (node (ref "U2") (pin "5") (pinfunction "VCC_5") (pintype "bidirectional"))
      (node (ref "U5") (pin "2") (pinfunction "IN_2") (pintype "bidirectional"))
      (node (ref "U8") (pin "2") (pinfunction "VIN_2") (pintype "bidirectional"))
    )
    (net (code "98") (name "VCCIO") (class "Default")
      (node (ref "C16") (pin "2") (pinfunction "2_2") (pintype "passive"))
      (node (ref "C8") (pin "2") (pinfunction "2_2") (pintype "passive"))
      (node (ref "OP1") (pin "1") (pinfunction "A_1") (pintype "passive"))
      (node (ref "TP2") (pin "1") (pinfunction "1_1") (pintype "passive"))
      (node (ref "U5") (pin "1") (pinfunction "OUT_1") (pintype "bidirectional"))
    )
    (net (code "99") (name "unconnected-(D3-A-Pad1)") (class "Default")
      (node (ref "D3") (pin "1") (pinfunction "A_1") (pintype "passive"))
    )
    (net (code "100") (name "unconnected-(S2-Pad1)") (class "Default")
      (node (ref "S2") (pin "1") (pinfunction "1_1") (pintype "passive"))
    )
    (net (code "101") (name "unconnected-(S2-Pad3)") (class "Default")
      (node (ref "S2") (pin "3") (pinfunction "3_3") (pintype "passive"))
    )
  )
)
